# Encoder_USBC.net
KiCad netlist of a schematic drawn in Altium Designer
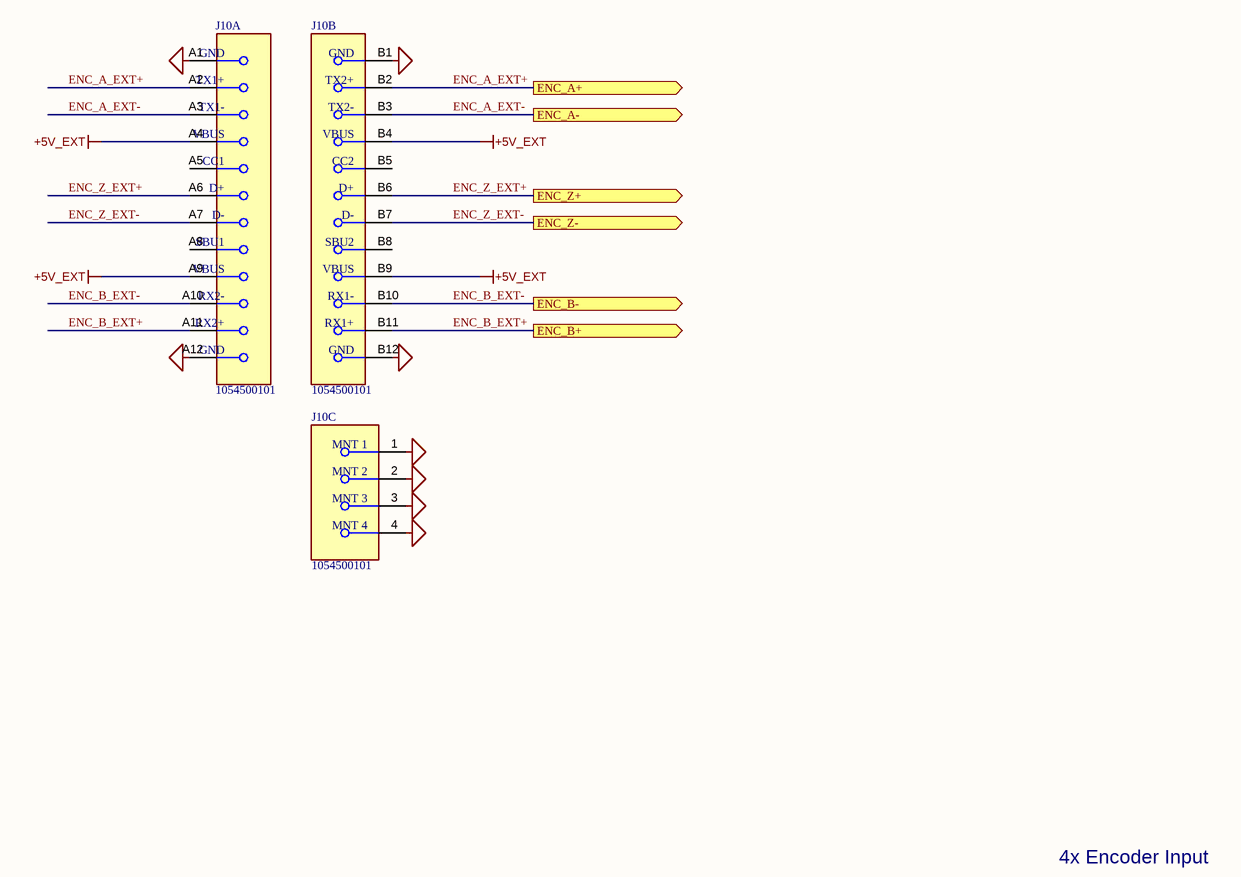
[diagram p0: Encoder_USBC.SchDoc]

(export (version "E")
  (design (tool "Eeschema 10.0.6"))
  (components
    (comp (ref "J10")
      (value "1054500101")
      (footprint "FP-1054500101-MFG")
      (description "CONN RCP USB3.1 TYPEC 24P SMD RA")
      (fields
        (field (name "MANUFACTURER") "Molex")
        (field (name "OCTOPART") "https://octopart.com/105450-0101-molex-68082325")
      )
      (libsource (lib "Universal_CNC_Breakout") (part "MOLEX-USBC"))
    )
  )
  (nets
    (net (code "1") (name "+5V_EXT") (class "Default")
      (node (ref "J10") (pin "A4") (pinfunction "VBUS_A4") (pintype "passive"))
      (node (ref "J10") (pin "A9") (pinfunction "VBUS_A9") (pintype "passive"))
      (node (ref "J10") (pin "B4") (pinfunction "VBUS_B4") (pintype "passive"))
      (node (ref "J10") (pin "B9") (pinfunction "VBUS_B9") (pintype "passive"))
    )
    (net (code "2") (name "/ENC_A_EXT+") (class "Default")
      (node (ref "J10") (pin "A2") (pinfunction "TX1+_A2") (pintype "passive"))
      (node (ref "J10") (pin "B2") (pinfunction "TX2+_B2") (pintype "passive"))
    )
    (net (code "3") (name "/ENC_A_EXT-") (class "Default")
      (node (ref "J10") (pin "A3") (pinfunction "TX1-_A3") (pintype "passive"))
      (node (ref "J10") (pin "B3") (pinfunction "TX2-_B3") (pintype "passive"))
    )
    (net (code "4") (name "/ENC_B_EXT+") (class "Default")
      (node (ref "J10") (pin "A11") (pinfunction "RX2+_A11") (pintype "passive"))
      (node (ref "J10") (pin "B11") (pinfunction "RX1+_B11") (pintype "passive"))
    )
    (net (code "5") (name "/ENC_B_EXT-") (class "Default")
      (node (ref "J10") (pin "A10") (pinfunction "RX2-_A10") (pintype "passive"))
      (node (ref "J10") (pin "B10") (pinfunction "RX1-_B10") (pintype "passive"))
    )
    (net (code "6") (name "/ENC_Z_EXT+") (class "Default")
      (node (ref "J10") (pin "A6") (pinfunction "D+_A6") (pintype "passive"))
      (node (ref "J10") (pin "B6") (pinfunction "D+_B6") (pintype "passive"))
    )
    (net (code "7") (name "/ENC_Z_EXT-") (class "Default")
      (node (ref "J10") (pin "A7") (pinfunction "D-_A7") (pintype "passive"))
      (node (ref "J10") (pin "B7") (pinfunction "D-_B7") (pintype "passive"))
    )
    (net (code "8") (name "GND_EXT") (class "Default")
      (node (ref "J10") (pin "1") (pinfunction "MNT_1_1") (pintype "passive"))
      (node (ref "J10") (pin "2") (pinfunction "MNT_2_2") (pintype "passive"))
      (node (ref "J10") (pin "3") (pinfunction "MNT_3_3") (pintype "passive"))
      (node (ref "J10") (pin "4") (pinfunction "MNT_4_4") (pintype "passive"))
      (node (ref "J10") (pin "A1") (pinfunction "GND_A1") (pintype "passive"))
      (node (ref "J10") (pin "A12") (pinfunction "GND_A12") (pintype "passive"))
      (node (ref "J10") (pin "B1") (pinfunction "GND_B1") (pintype "passive"))
      (node (ref "J10") (pin "B12") (pinfunction "GND_B12") (pintype "passive"))
    )
    (net (code "9") (name "unconnected-(J10A-CC1-PadA5)") (class "Default")
      (node (ref "J10") (pin "A5") (pinfunction "CC1_A5") (pintype "passive"))
    )
    (net (code "10") (name "unconnected-(J10A-SBU1-PadA8)") (class "Default")
      (node (ref "J10") (pin "A8") (pinfunction "SBU1_A8") (pintype "passive"))
    )
    (net (code "11") (name "unconnected-(J10B-CC2-PadB5)") (class "Default")
      (node (ref "J10") (pin "B5") (pinfunction "CC2_B5") (pintype "passive"))
    )
    (net (code "12") (name "unconnected-(J10B-SBU2-PadB8)") (class "Default")
      (node (ref "J10") (pin "B8") (pinfunction "SBU2_B8") (pintype "passive"))
    )
  )
)
